# Power-Supply-lm2576.net
KiCad netlist of a schematic drawn in EasyEDA
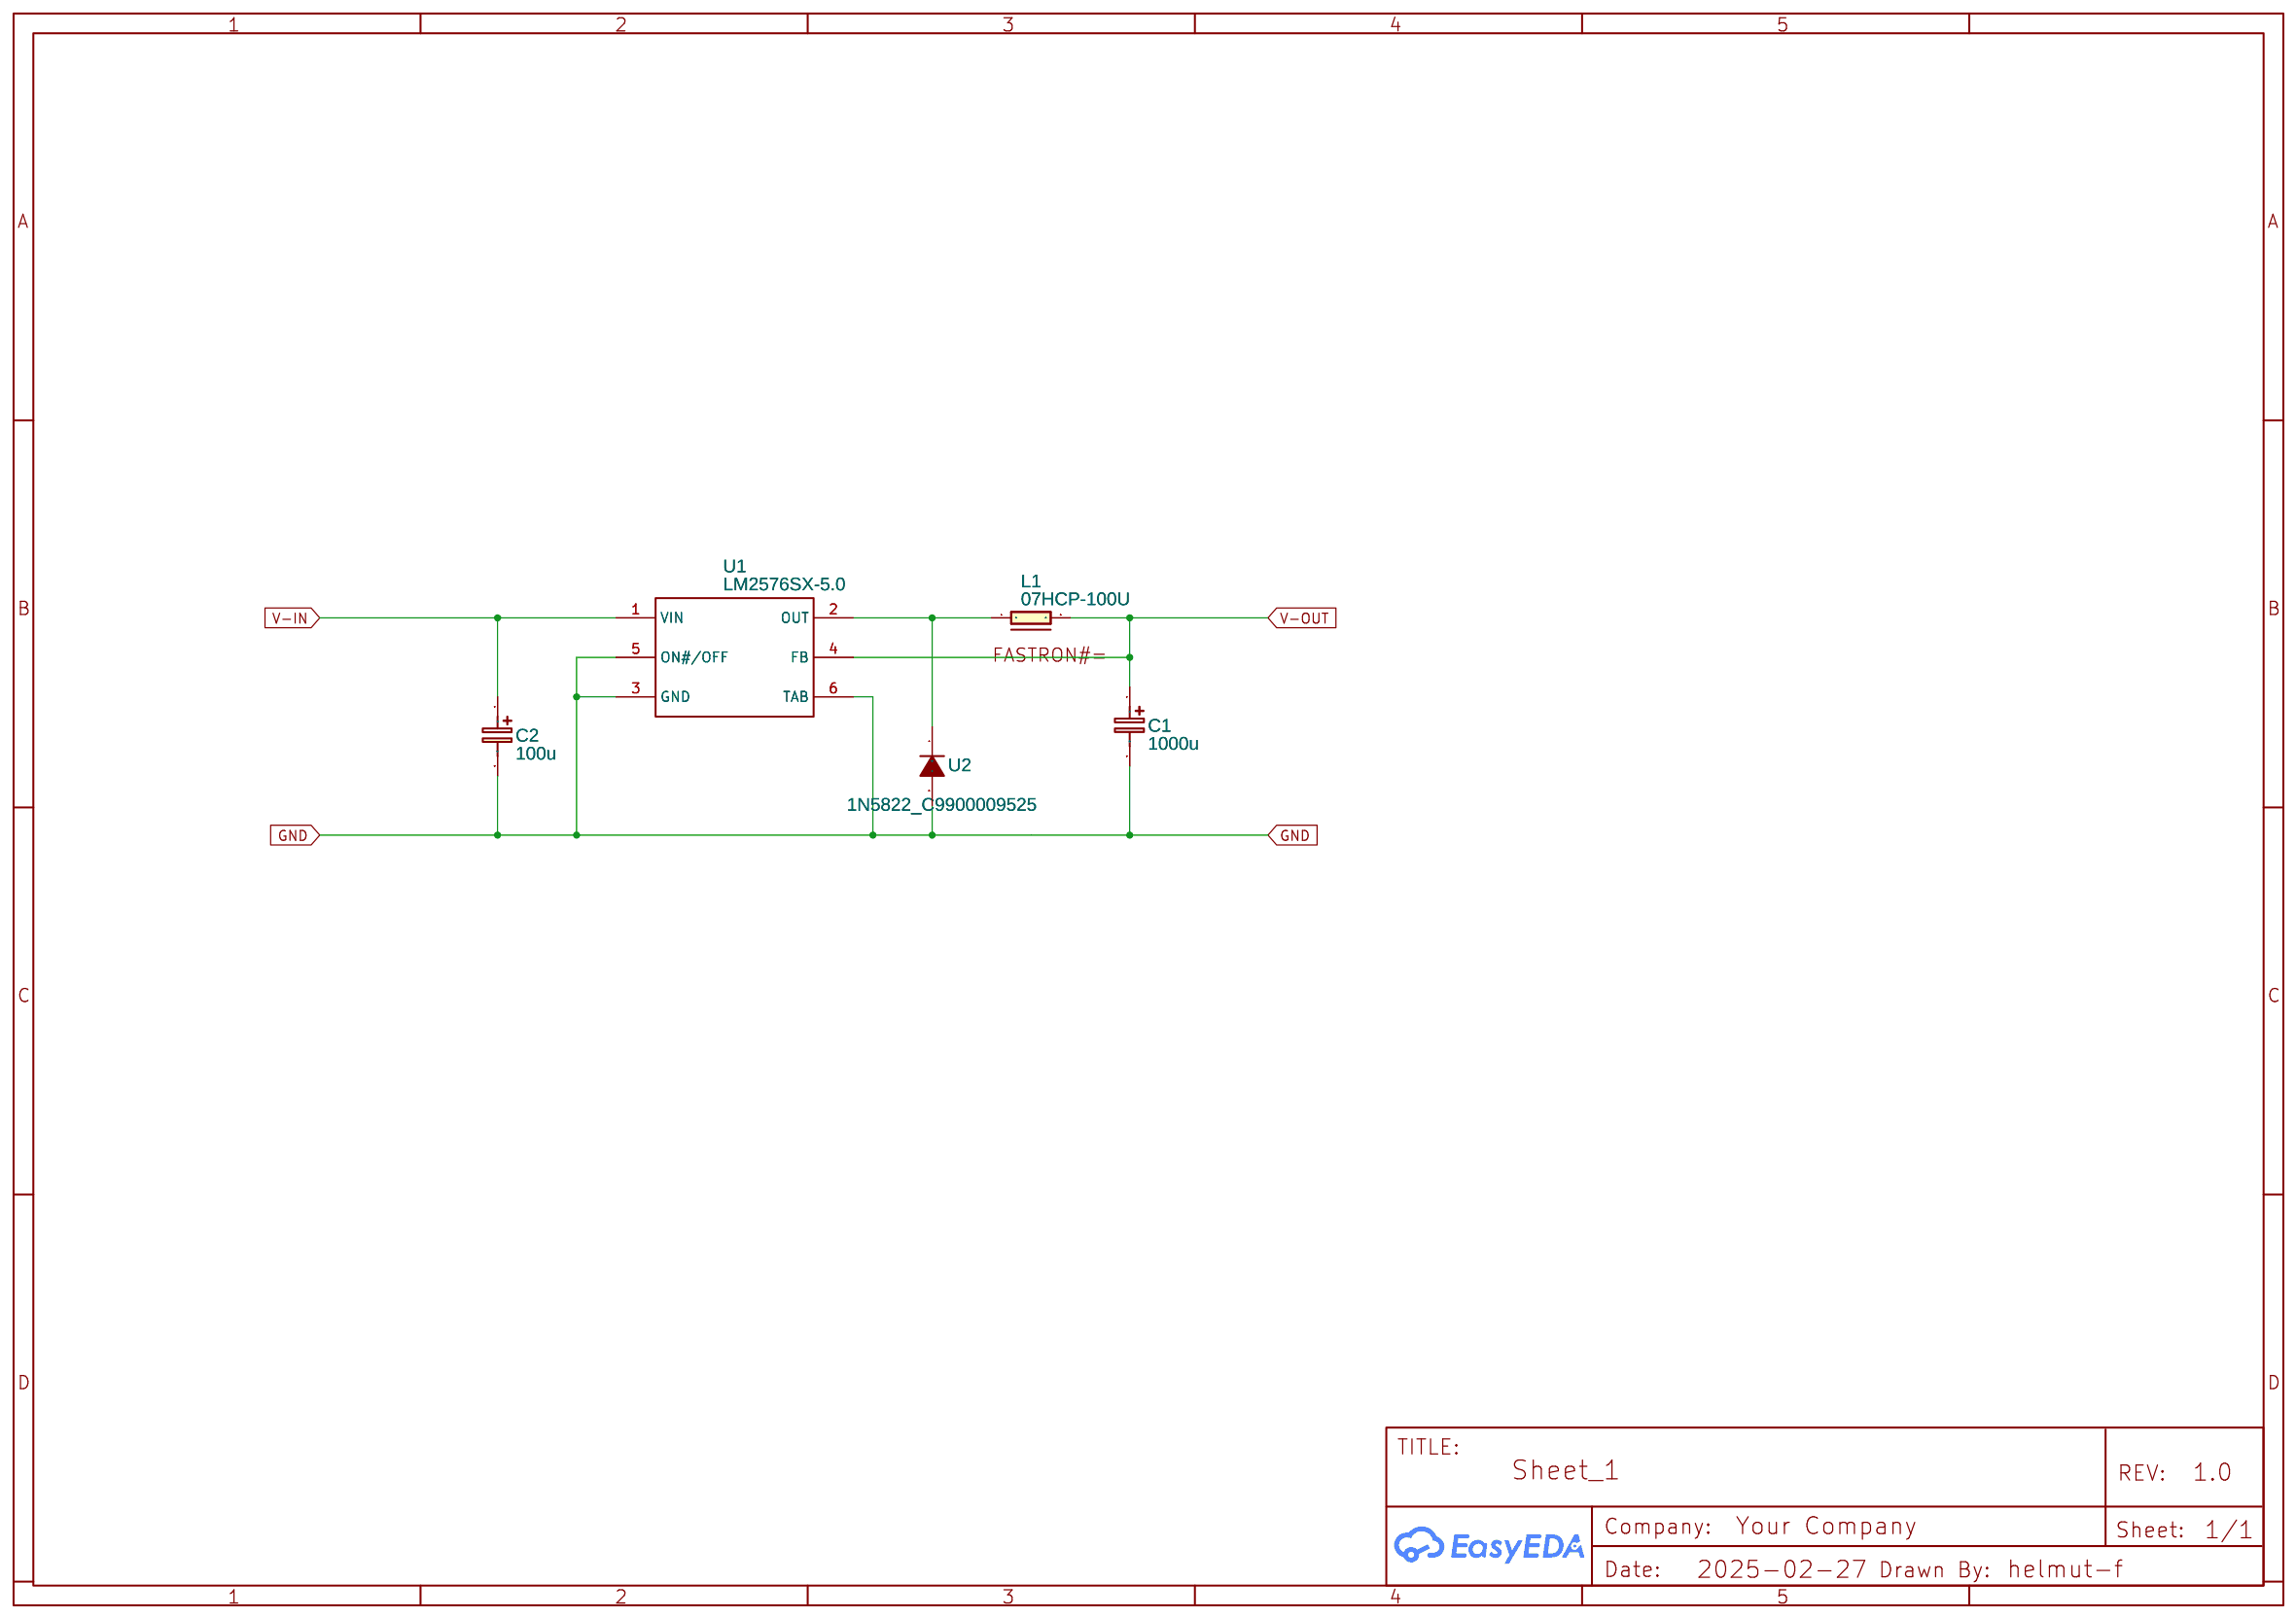
[diagram p0: schematic sheet]

(export (version "E")
  (design (tool "Eeschema 10.0.6"))
  (components
    (comp (ref "C1") (value "1000u") (libsource (lib "") (part "CE_SMD_D8.0×H10.5_EU")))
    (comp (ref "C2") (value "100u") (libsource (lib "") (part "CE_SMD_D8.0×H10.5_EU_1")))
    (comp (ref "L1") (value "07HCP-100U") (libsource (lib "") (part "07HCP-100U")))
    (comp (ref "U1")
      (value "LM2576SX-5.0")
      (fields (field (name "Manufacturer Part") "LM2576SX-5.0/NOPB") (field (name "Manufacturer") "TI(德州仪器)"))
      (libsource (lib "") (part "LM2576SX-5.0"))
    )
    (comp (ref "U2")
      (value "1N5822_C9900009525")
      (fields (field (name "Manufacturer Part") "1N5822"))
      (libsource (lib "") (part "1N5822_C9900009525"))
    )
  )
  (nets
    (net (code "1") (name "GND") (class "Default")
      (node (ref "C1") (pin "2") (pinfunction "2_2") (pintype "unspecified"))
      (node (ref "C2") (pin "2") (pinfunction "2_2") (pintype "unspecified"))
      (node (ref "U1") (pin "3") (pinfunction "GND_3") (pintype "passive"))
      (node (ref "U1") (pin "5") (pinfunction "ON#/OFF_5") (pintype "unspecified"))
      (node (ref "U1") (pin "6") (pinfunction "TAB_6") (pintype "passive"))
      (node (ref "U2") (pin "2") (pinfunction "A_2") (pintype "unspecified"))
    )
    (net (code "2") (name "Net-(U1-OUT)") (class "Default")
      (node (ref "L1") (pin "1") (pinfunction "1_1") (pintype "unspecified"))
      (node (ref "U1") (pin "2") (pinfunction "OUT_2") (pintype "passive"))
      (node (ref "U2") (pin "1") (pinfunction "C_1") (pintype "unspecified"))
    )
    (net (code "3") (name "V-IN") (class "Default")
      (node (ref "C2") (pin "1") (pinfunction "1_1") (pintype "unspecified"))
      (node (ref "U1") (pin "1") (pinfunction "VIN_1") (pintype "passive"))
    )
    (net (code "4") (name "V-OUT") (class "Default")
      (node (ref "C1") (pin "1") (pinfunction "1_1") (pintype "unspecified"))
      (node (ref "L1") (pin "2") (pinfunction "2_2") (pintype "unspecified"))
      (node (ref "U1") (pin "4") (pinfunction "FB_4") (pintype "unspecified"))
    )
  )
)
